# Sheet1.net
KiCad netlist of a schematic drawn in Altium Designer
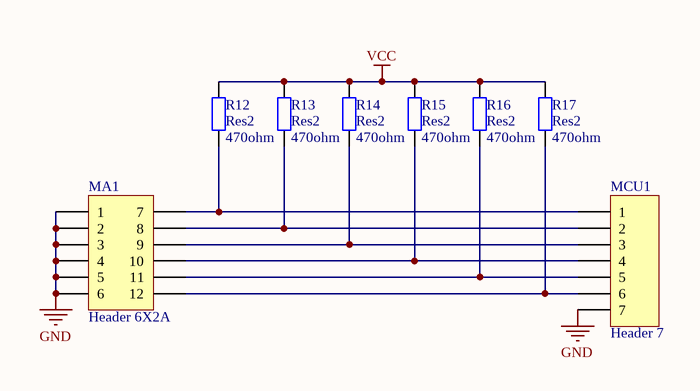
[diagram p0: Sheet1.SchDoc]

(export (version "E")
  (design (tool "Eeschema 10.0.6"))
  (components
    (comp (ref "MA1")
      (value "Header 6X2A")
      (footprint "HDR2X6_CEN")
      (description "Header, 6-Pin, Dual row")
      (fields (field (name "PUBLISHER") "Altium Limited"))
      (libsource (lib "Miscellaneous Connectors") (part "Header 6X2A"))
    )
    (comp (ref "MCU1")
      (value "Header 7")
      (footprint "HDR1X7")
      (description "Header, 7-Pin")
      (fields (field (name "PUBLISHER") "Altium Limited"))
      (libsource (lib "Miscellaneous Connectors") (part "Header 7"))
    )
    (comp (ref "R12")
      (value "Res2")
      (footprint "AXIAL-0.4")
      (description "Resistor")
      (fields (field (name "ALTIUM_VALUE") "470ohm") (field (name "PUBLISHER") "Altium Limited"))
      (libsource (lib "Miscellaneous Devices") (part "Res2"))
    )
    (comp (ref "R13")
      (value "Res2")
      (footprint "AXIAL-0.4")
      (description "Resistor")
      (fields (field (name "ALTIUM_VALUE") "470ohm") (field (name "PUBLISHER") "Altium Limited"))
      (libsource (lib "Miscellaneous Devices") (part "Res2"))
    )
    (comp (ref "R14")
      (value "Res2")
      (footprint "AXIAL-0.4")
      (description "Resistor")
      (fields (field (name "ALTIUM_VALUE") "470ohm") (field (name "PUBLISHER") "Altium Limited"))
      (libsource (lib "Miscellaneous Devices") (part "Res2"))
    )
    (comp (ref "R15")
      (value "Res2")
      (footprint "AXIAL-0.4")
      (description "Resistor")
      (fields (field (name "ALTIUM_VALUE") "470ohm") (field (name "PUBLISHER") "Altium Limited"))
      (libsource (lib "Miscellaneous Devices") (part "Res2"))
    )
    (comp (ref "R16")
      (value "Res2")
      (footprint "AXIAL-0.4")
      (description "Resistor")
      (fields (field (name "ALTIUM_VALUE") "470ohm") (field (name "PUBLISHER") "Altium Limited"))
      (libsource (lib "Miscellaneous Devices") (part "Res2"))
    )
    (comp (ref "R17")
      (value "Res2")
      (footprint "AXIAL-0.4")
      (description "Resistor")
      (fields (field (name "ALTIUM_VALUE") "470ohm") (field (name "PUBLISHER") "Altium Limited"))
      (libsource (lib "Miscellaneous Devices") (part "Res2"))
    )
  )
  (nets
    (net (code "1") (name "GND") (class "Default")
      (node (ref "MA1") (pin "1") (pinfunction "1_1") (pintype "passive"))
      (node (ref "MA1") (pin "2") (pinfunction "2_2") (pintype "passive"))
      (node (ref "MA1") (pin "3") (pinfunction "3_3") (pintype "passive"))
      (node (ref "MA1") (pin "4") (pinfunction "4_4") (pintype "passive"))
      (node (ref "MA1") (pin "5") (pinfunction "5_5") (pintype "passive"))
      (node (ref "MA1") (pin "6") (pinfunction "6_6") (pintype "passive"))
      (node (ref "MCU1") (pin "7") (pinfunction "7_7") (pintype "passive"))
    )
    (net (code "2") (name "Net-(MA1-Pad7)") (class "Default")
      (node (ref "MA1") (pin "7") (pinfunction "7_7") (pintype "passive"))
      (node (ref "MCU1") (pin "1") (pinfunction "1_1") (pintype "passive"))
      (node (ref "R12") (pin "1") (pinfunction "1_1") (pintype "passive"))
    )
    (net (code "3") (name "Net-(MA1-Pad8)") (class "Default")
      (node (ref "MA1") (pin "8") (pinfunction "8_8") (pintype "passive"))
      (node (ref "MCU1") (pin "2") (pinfunction "2_2") (pintype "passive"))
      (node (ref "R13") (pin "1") (pinfunction "1_1") (pintype "passive"))
    )
    (net (code "4") (name "Net-(MA1-Pad9)") (class "Default")
      (node (ref "MA1") (pin "9") (pinfunction "9_9") (pintype "passive"))
      (node (ref "MCU1") (pin "3") (pinfunction "3_3") (pintype "passive"))
      (node (ref "R14") (pin "1") (pinfunction "1_1") (pintype "passive"))
    )
    (net (code "5") (name "Net-(MA1-Pad10)") (class "Default")
      (node (ref "MA1") (pin "10") (pinfunction "10_10") (pintype "passive"))
      (node (ref "MCU1") (pin "4") (pinfunction "4_4") (pintype "passive"))
      (node (ref "R15") (pin "1") (pinfunction "1_1") (pintype "passive"))
    )
    (net (code "6") (name "Net-(MA1-Pad11)") (class "Default")
      (node (ref "MA1") (pin "11") (pinfunction "11_11") (pintype "passive"))
      (node (ref "MCU1") (pin "5") (pinfunction "5_5") (pintype "passive"))
      (node (ref "R16") (pin "1") (pinfunction "1_1") (pintype "passive"))
    )
    (net (code "7") (name "Net-(MA1-Pad12)") (class "Default")
      (node (ref "MA1") (pin "12") (pinfunction "12_12") (pintype "passive"))
      (node (ref "MCU1") (pin "6") (pinfunction "6_6") (pintype "passive"))
      (node (ref "R17") (pin "1") (pinfunction "1_1") (pintype "passive"))
    )
    (net (code "8") (name "VCC") (class "Default")
      (node (ref "R12") (pin "2") (pinfunction "2_2") (pintype "passive"))
      (node (ref "R13") (pin "2") (pinfunction "2_2") (pintype "passive"))
      (node (ref "R14") (pin "2") (pinfunction "2_2") (pintype "passive"))
      (node (ref "R15") (pin "2") (pinfunction "2_2") (pintype "passive"))
      (node (ref "R16") (pin "2") (pinfunction "2_2") (pintype "passive"))
      (node (ref "R17") (pin "2") (pinfunction "2_2") (pintype "passive"))
    )
  )
)
